# MCU.net
KiCad netlist of a schematic drawn in Altium Designer
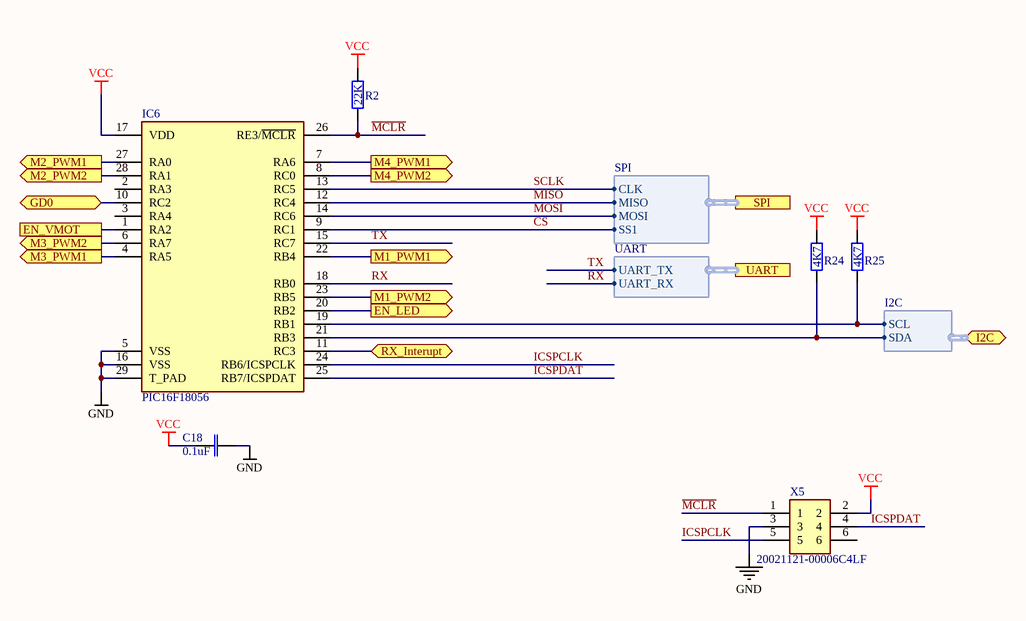
[diagram p0: MCU.SchDoc]

(export (version "E")
  (design (tool "Eeschema 10.0.6"))
  (components
    (comp (ref "C18")
      (value "0.1uF")
      (footprint "CAP0402")
      (fields (field (name "MANUFACTURER") "Samsung Electro-Mechanics"))
      (libsource (lib "Schematic") (part "CAP_0402"))
    )
    (comp (ref "IC6")
      (value "PIC16F18056")
      (footprint "QFN28_4X4(PIC16F18056)")
      (fields (field (name "MANUFACTURER") "Microchip Technology"))
      (libsource (lib "Schematic") (part "PIC16F18056"))
    )
    (comp (ref "R2")
      (value "22K")
      (footprint "RES0402")
      (fields (field (name "MANUFACTURER") "YAGEO"))
      (libsource (lib "Schematic") (part "RES_0402"))
    )
    (comp (ref "R24")
      (value "4K7")
      (footprint "RES0402")
      (fields (field (name "MANUFACTURER") "YAGEO"))
      (libsource (lib "Schematic") (part "RES_0402"))
    )
    (comp (ref "R25")
      (value "4K7")
      (footprint "RES0402")
      (fields (field (name "MANUFACTURER") "YAGEO"))
      (libsource (lib "Schematic") (part "RES_0402"))
    )
    (comp (ref "X5")
      (value "20021121-00006C4LF")
      (footprint "20021121-00X06CXLF")
      (fields (field (name "JLCPCB PART #") "C178291") (field (name "MANUFACTURER") "Amphenol ICC (FCI)"))
      (libsource (lib "Schematic") (part "20021121-00006C4LF"))
    )
  )
  (nets
    (net (code "4") (name "/CS") (class "Default")
      (node (ref "IC6") (pin "9") (pinfunction "RC1_9") (pintype "passive"))
    )
    (net (code "5") (name "/EN_LED") (class "Default")
      (node (ref "IC6") (pin "20") (pinfunction "RB2_20") (pintype "passive"))
    )
    (net (code "6") (name "/EN_VMOT") (class "Default")
      (node (ref "IC6") (pin "1") (pinfunction "RA2_1") (pintype "passive"))
    )
    (net (code "7") (name "/GD0") (class "Default")
      (node (ref "IC6") (pin "10") (pinfunction "RC2_10") (pintype "passive"))
    )
    (net (code "8") (name "/ICSPCLK") (class "Default")
      (node (ref "IC6") (pin "24") (pinfunction "RB6/ICSPCLK_24") (pintype "passive"))
      (node (ref "X5") (pin "5") (pinfunction "5_5") (pintype "passive"))
    )
    (net (code "9") (name "/ICSPDAT") (class "Default")
      (node (ref "IC6") (pin "25") (pinfunction "RB7/ICSPDAT_25") (pintype "passive"))
      (node (ref "X5") (pin "4") (pinfunction "4_4") (pintype "passive"))
    )
    (net (code "10") (name "/M1_PWM1") (class "Default")
      (node (ref "IC6") (pin "22") (pinfunction "RB4_22") (pintype "passive"))
    )
    (net (code "11") (name "/M1_PWM2") (class "Default")
      (node (ref "IC6") (pin "23") (pinfunction "RB5_23") (pintype "passive"))
    )
    (net (code "12") (name "/M2_PWM1") (class "Default")
      (node (ref "IC6") (pin "27") (pinfunction "RA0_27") (pintype "passive"))
    )
    (net (code "13") (name "/M2_PWM2") (class "Default")
      (node (ref "IC6") (pin "28") (pinfunction "RA1_28") (pintype "passive"))
    )
    (net (code "14") (name "/M3_PWM1") (class "Default")
      (node (ref "IC6") (pin "4") (pinfunction "RA5_4") (pintype "passive"))
    )
    (net (code "15") (name "/M3_PWM2") (class "Default")
      (node (ref "IC6") (pin "6") (pinfunction "RA7_6") (pintype "passive"))
    )
    (net (code "16") (name "/M4_PWM1") (class "Default")
      (node (ref "IC6") (pin "7") (pinfunction "RA6_7") (pintype "passive"))
    )
    (net (code "17") (name "/M4_PWM2") (class "Default")
      (node (ref "IC6") (pin "8") (pinfunction "RC0_8") (pintype "passive"))
    )
    (net (code "18") (name "/MISO") (class "Default")
      (node (ref "IC6") (pin "12") (pinfunction "RC4_12") (pintype "passive"))
    )
    (net (code "19") (name "/MOSI") (class "Default")
      (node (ref "IC6") (pin "14") (pinfunction "RC6_14") (pintype "passive"))
    )
    (net (code "20") (name "/RX") (class "Default")
      (node (ref "IC6") (pin "18") (pinfunction "RB0_18") (pintype "passive"))
    )
    (net (code "21") (name "/RX_Interupt") (class "Default")
      (node (ref "IC6") (pin "11") (pinfunction "RC3_11") (pintype "passive"))
    )
    (net (code "22") (name "/SCLK") (class "Default")
      (node (ref "IC6") (pin "13") (pinfunction "RC5_13") (pintype "passive"))
    )
    (net (code "23") (name "/TX") (class "Default")
      (node (ref "IC6") (pin "15") (pinfunction "RC7_15") (pintype "passive"))
    )
    (net (code "27") (name "/~{MCLR}") (class "Default")
      (node (ref "IC6") (pin "26") (pinfunction "RE3/~{MCLR}_26") (pintype "passive"))
      (node (ref "R2") (pin "1") (pinfunction "1_1") (pintype "passive"))
      (node (ref "X5") (pin "1") (pinfunction "1_1") (pintype "passive"))
    )
    (net (code "28") (name "GND") (class "Default")
      (node (ref "C18") (pin "2") (pinfunction "2_2") (pintype "passive"))
      (node (ref "IC6") (pin "16") (pinfunction "VSS_16") (pintype "passive"))
      (node (ref "IC6") (pin "29") (pinfunction "T_PAD_29") (pintype "passive"))
      (node (ref "IC6") (pin "5") (pinfunction "VSS_5") (pintype "passive"))
      (node (ref "X5") (pin "3") (pinfunction "3_3") (pintype "passive"))
    )
    (net (code "29") (name "Net-(IC6-RB1)") (class "Default")
      (node (ref "IC6") (pin "19") (pinfunction "RB1_19") (pintype "passive"))
      (node (ref "R25") (pin "1") (pinfunction "1_1") (pintype "passive"))
    )
    (net (code "30") (name "Net-(IC6-RB3)") (class "Default")
      (node (ref "IC6") (pin "21") (pinfunction "RB3_21") (pintype "passive"))
      (node (ref "R24") (pin "1") (pinfunction "1_1") (pintype "passive"))
    )
    (net (code "31") (name "VCC") (class "Default")
      (node (ref "C18") (pin "1") (pinfunction "1_1") (pintype "passive"))
      (node (ref "IC6") (pin "17") (pinfunction "VDD_17") (pintype "passive"))
      (node (ref "R2") (pin "2") (pinfunction "2_2") (pintype "passive"))
      (node (ref "R24") (pin "2") (pinfunction "2_2") (pintype "passive"))
      (node (ref "R25") (pin "2") (pinfunction "2_2") (pintype "passive"))
      (node (ref "X5") (pin "2") (pinfunction "2_2") (pintype "passive"))
    )
    (net (code "32") (name "unconnected-(IC6-RA3-Pad2)") (class "Default")
      (node (ref "IC6") (pin "2") (pinfunction "RA3_2") (pintype "passive"))
    )
    (net (code "33") (name "unconnected-(IC6-RA4-Pad3)") (class "Default")
      (node (ref "IC6") (pin "3") (pinfunction "RA4_3") (pintype "passive"))
    )
    (net (code "34") (name "unconnected-(X5-Pad6)") (class "Default")
      (node (ref "X5") (pin "6") (pinfunction "6_6") (pintype "passive"))
    )
  )
)
